# Datasheet.net
KiCad netlist of a schematic drawn in Altium Designer
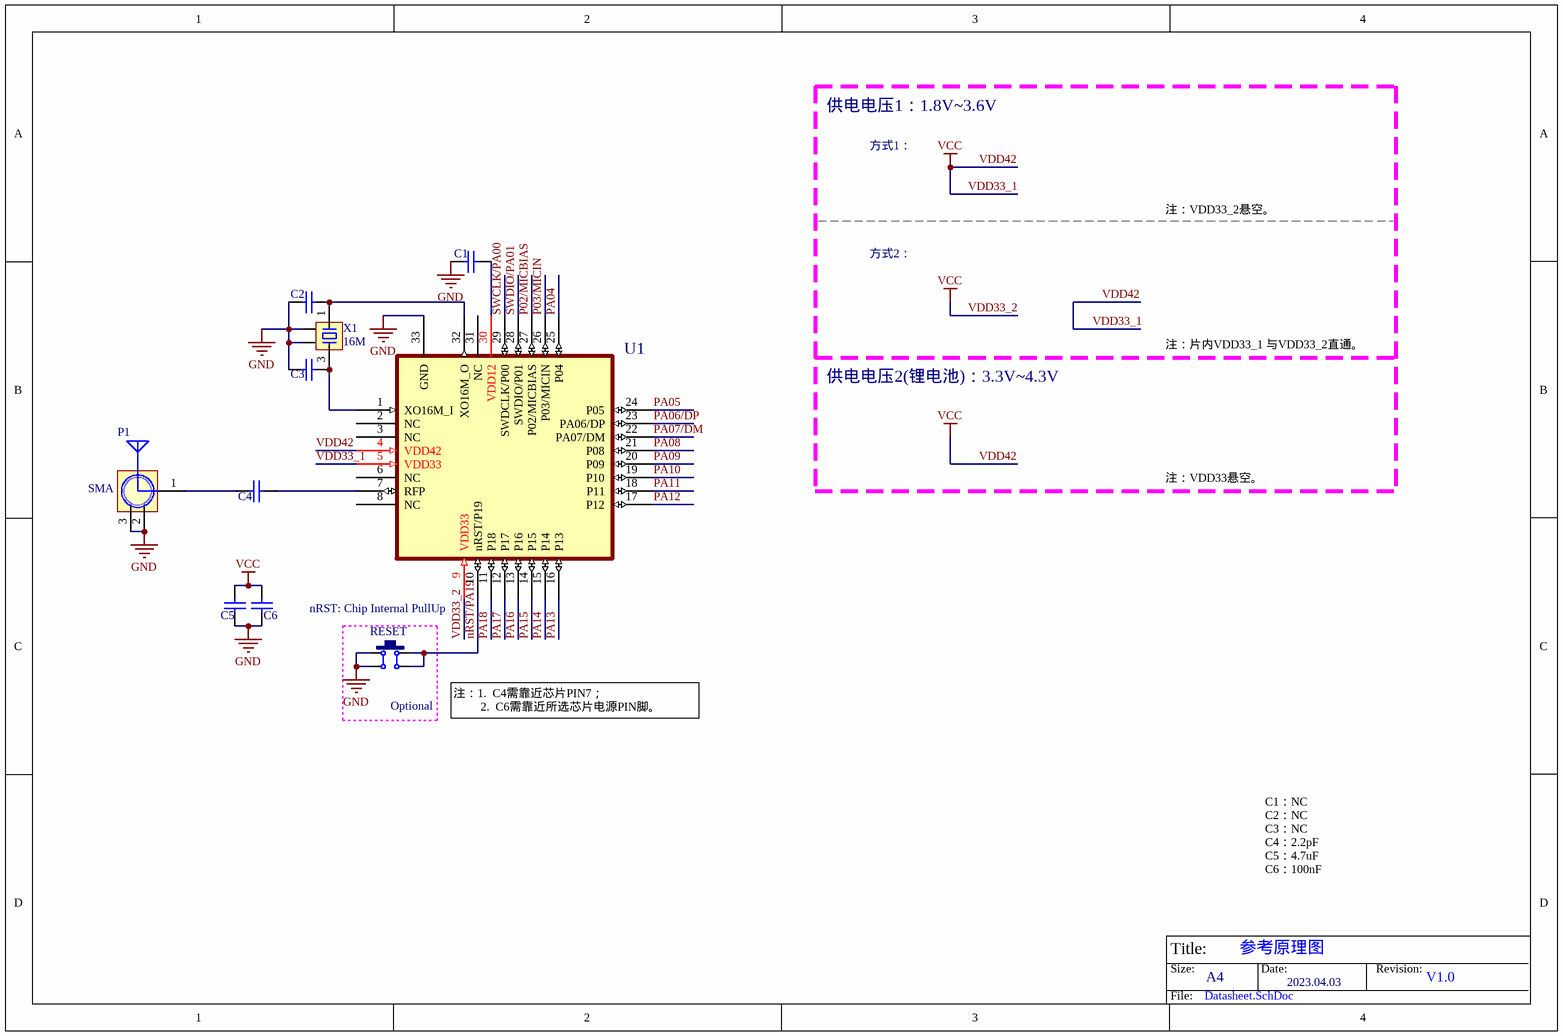
[diagram p0: Datasheet.SchDoc]

(export (version "E")
  (design (tool "Eeschema 10.0.6"))
  (components
    (comp (ref "C1")
      (value "NC")
      (footprint "C0402")
      (description "Capacitor (Semiconductor SIM Model)")
      (libsource (lib "HYBXX_Dragon") (part "Cap"))
    )
    (comp (ref "C2")
      (value "NC")
      (footprint "C0402")
      (description "Capacitor (Semiconductor SIM Model)")
      (libsource (lib "HYBXX_Dragon") (part "Cap"))
    )
    (comp (ref "C3")
      (value "NC")
      (footprint "C0402")
      (description "Capacitor (Semiconductor SIM Model)")
      (libsource (lib "HYBXX_Dragon") (part "Cap"))
    )
    (comp (ref "C4")
      (value "0")
      (footprint "C0402")
      (description "Capacitor (Semiconductor SIM Model)")
      (libsource (lib "HYBXX_Dragon") (part "Cap"))
    )
    (comp (ref "C5")
      (value "NC")
      (footprint "C0402")
      (description "Capacitor (Semiconductor SIM Model)")
      (libsource (lib "HYBXX_Dragon") (part "Cap"))
    )
    (comp (ref "C6")
      (value "NC")
      (footprint "C0402")
      (description "Capacitor (Semiconductor SIM Model)")
      (libsource (lib "HYBXX_Dragon") (part "Cap"))
    )
    (comp (ref "P1")
      (value "SMA")
      (footprint "SMA-KE-LI")
      (description "SMA-2.4G射频天线接口")
      (libsource (lib "1.8 - WiFi天线-SMA射频座") (part "SMA"))
    )
    (comp (ref "RESET")
      (value "6x6x5")
      (footprint "TSW SMD-6*6*4.3")
      (description "贴片6x6轻触开关")
      (fields (field (name "版权归属") "封装库来自淘宝 ID：黄晶宝石"))
      (libsource (lib "0.7 - 常用按键-开关") (part "TSW SMD-6x6"))
    )
    (comp (ref "U1")
      (value "C1_QFN32")
      (footprint "QFN32L_0404x0.75-0.40")
      (description "HY Dragon C 蓝牙芯片, QFN32_4x4")
      (libsource (lib "HYBXX_Dragon") (part "C1_QFN32"))
    )
    (comp (ref "X1")
      (value "16M")
      (footprint "SMD3225")
      (description "4脚无源晶振")
      (fields (field (name "版权归属") "封装库来自淘宝卖家 ID：黄晶宝石"))
      (libsource (lib "2.0 - 保险丝-晶振-光耦") (part "XTAL-4P"))
    )
  )
  (nets
    (net (code "1") (name "/P02{slash}MICBIAS") (class "Default")
      (node (ref "U1") (pin "27") (pinfunction "P02/MICBIAS_27") (pintype "bidirectional"))
    )
    (net (code "2") (name "/P03{slash}MICIN") (class "Default")
      (node (ref "U1") (pin "26") (pinfunction "P03/MICIN_26") (pintype "bidirectional"))
    )
    (net (code "3") (name "/PA04") (class "Default")
      (node (ref "U1") (pin "25") (pinfunction "P04_25") (pintype "bidirectional"))
    )
    (net (code "4") (name "/PA05") (class "Default")
      (node (ref "U1") (pin "24") (pinfunction "P05_24") (pintype "bidirectional"))
    )
    (net (code "5") (name "/PA06{slash}DP") (class "Default")
      (node (ref "U1") (pin "23") (pinfunction "PA06/DP_23") (pintype "bidirectional"))
    )
    (net (code "6") (name "/PA07{slash}DM") (class "Default")
      (node (ref "U1") (pin "22") (pinfunction "PA07/DM_22") (pintype "bidirectional"))
    )
    (net (code "7") (name "/PA08") (class "Default")
      (node (ref "U1") (pin "21") (pinfunction "P08_21") (pintype "bidirectional"))
    )
    (net (code "8") (name "/PA09") (class "Default")
      (node (ref "U1") (pin "20") (pinfunction "P09_20") (pintype "bidirectional"))
    )
    (net (code "9") (name "/PA10") (class "Default")
      (node (ref "U1") (pin "19") (pinfunction "P10_19") (pintype "bidirectional"))
    )
    (net (code "10") (name "/PA11") (class "Default")
      (node (ref "U1") (pin "18") (pinfunction "P11_18") (pintype "bidirectional"))
    )
    (net (code "11") (name "/PA12") (class "Default")
      (node (ref "U1") (pin "17") (pinfunction "P12_17") (pintype "bidirectional"))
    )
    (net (code "12") (name "/PA13") (class "Default")
      (node (ref "U1") (pin "16") (pinfunction "P13_16") (pintype "bidirectional"))
    )
    (net (code "13") (name "/PA14") (class "Default")
      (node (ref "U1") (pin "15") (pinfunction "P14_15") (pintype "bidirectional"))
    )
    (net (code "14") (name "/PA15") (class "Default")
      (node (ref "U1") (pin "14") (pinfunction "P15_14") (pintype "bidirectional"))
    )
    (net (code "15") (name "/PA16") (class "Default")
      (node (ref "U1") (pin "13") (pinfunction "P16_13") (pintype "bidirectional"))
    )
    (net (code "16") (name "/PA17") (class "Default")
      (node (ref "U1") (pin "12") (pinfunction "P17_12") (pintype "bidirectional"))
    )
    (net (code "17") (name "/PA18") (class "Default")
      (node (ref "U1") (pin "11") (pinfunction "P18_11") (pintype "bidirectional"))
    )
    (net (code "18") (name "/SWCLK{slash}PA00") (class "Default")
      (node (ref "U1") (pin "29") (pinfunction "SWDCLK/P00_29") (pintype "bidirectional"))
    )
    (net (code "19") (name "/SWDIO{slash}PA01") (class "Default")
      (node (ref "U1") (pin "28") (pinfunction "SWDIO/P01_28") (pintype "bidirectional"))
    )
    (net (code "20") (name "/nRST{slash}PA19") (class "Default")
      (node (ref "RESET") (pin "2") (pinfunction "2_2") (pintype "passive"))
      (node (ref "RESET") (pin "3") (pinfunction "3_3") (pintype "passive"))
      (node (ref "U1") (pin "10") (pinfunction "nRST/P19_10") (pintype "bidirectional"))
    )
    (net (code "21") (name "GND") (class "Default")
      (node (ref "C1") (pin "2") (pinfunction "2_2") (pintype "passive"))
      (node (ref "C2") (pin "2") (pinfunction "2_2") (pintype "passive"))
      (node (ref "C3") (pin "2") (pinfunction "2_2") (pintype "passive"))
      (node (ref "C5") (pin "2") (pinfunction "2_2") (pintype "passive"))
      (node (ref "C6") (pin "2") (pinfunction "2_2") (pintype "passive"))
      (node (ref "P1") (pin "2") (pinfunction "GND_2") (pintype "power_in"))
      (node (ref "P1") (pin "3") (pinfunction "GND_3") (pintype "power_in"))
      (node (ref "RESET") (pin "1") (pinfunction "1_1") (pintype "passive"))
      (node (ref "RESET") (pin "4") (pinfunction "4_4") (pintype "passive"))
      (node (ref "U1") (pin "33") (pinfunction "GND_33") (pintype "passive"))
      (node (ref "X1") (pin "2") (pinfunction "2_2") (pintype "passive"))
      (node (ref "X1") (pin "4") (pinfunction "4_4") (pintype "passive"))
    )
    (net (code "22") (name "Net-(P1-ANT)") (class "Default")
      (node (ref "C4") (pin "2") (pinfunction "2_2") (pintype "passive"))
      (node (ref "P1") (pin "1") (pinfunction "ANT_1") (pintype "passive"))
    )
    (net (code "23") (name "Net-(U1-RFP)") (class "Default")
      (node (ref "C4") (pin "1") (pinfunction "1_1") (pintype "passive"))
      (node (ref "U1") (pin "7") (pinfunction "RFP_7") (pintype "bidirectional"))
    )
    (net (code "24") (name "Net-(U1-VDD12)") (class "Default")
      (node (ref "C1") (pin "1") (pinfunction "1_1") (pintype "passive"))
      (node (ref "U1") (pin "30") (pinfunction "VDD12_30") (pintype "passive"))
    )
    (net (code "25") (name "Net-(U1-XO16M_I)") (class "Default")
      (node (ref "C3") (pin "1") (pinfunction "1_1") (pintype "passive"))
      (node (ref "U1") (pin "1") (pinfunction "XO16M_I_1") (pintype "input"))
      (node (ref "X1") (pin "3") (pinfunction "3_3") (pintype "passive"))
    )
    (net (code "26") (name "Net-(U1-XO16M_O)") (class "Default")
      (node (ref "C2") (pin "1") (pinfunction "1_1") (pintype "passive"))
      (node (ref "U1") (pin "32") (pinfunction "XO16M_O_32") (pintype "output"))
      (node (ref "X1") (pin "1") (pinfunction "1_1") (pintype "passive"))
    )
    (net (code "27") (name "VCC") (class "Default")
      (node (ref "C5") (pin "1") (pinfunction "1_1") (pintype "passive"))
      (node (ref "C6") (pin "1") (pinfunction "1_1") (pintype "passive"))
      (node (ref "U1") (pin "4") (pinfunction "VDD42_4") (pintype "input"))
      (node (ref "U1") (pin "5") (pinfunction "VDD33_5") (pintype "input"))
      (node (ref "U1") (pin "9") (pinfunction "VDD33_9") (pintype "input"))
    )
    (net (code "28") (name "unconnected-(U1-NC-Pad2)") (class "Default")
      (node (ref "U1") (pin "2") (pinfunction "NC_2") (pintype "passive"))
    )
    (net (code "29") (name "unconnected-(U1-NC-Pad3)") (class "Default")
      (node (ref "U1") (pin "3") (pinfunction "NC_3") (pintype "open_emitter"))
    )
    (net (code "30") (name "unconnected-(U1-NC-Pad6)") (class "Default")
      (node (ref "U1") (pin "6") (pinfunction "NC_6") (pintype "passive"))
    )
    (net (code "31") (name "unconnected-(U1-NC-Pad8)") (class "Default")
      (node (ref "U1") (pin "8") (pinfunction "NC_8") (pintype "passive"))
    )
    (net (code "32") (name "unconnected-(U1-NC-Pad31)") (class "Default")
      (node (ref "U1") (pin "31") (pinfunction "NC_31") (pintype "passive"))
    )
  )
)
